# Schematic.net
KiCad netlist of a schematic drawn in Altium Designer
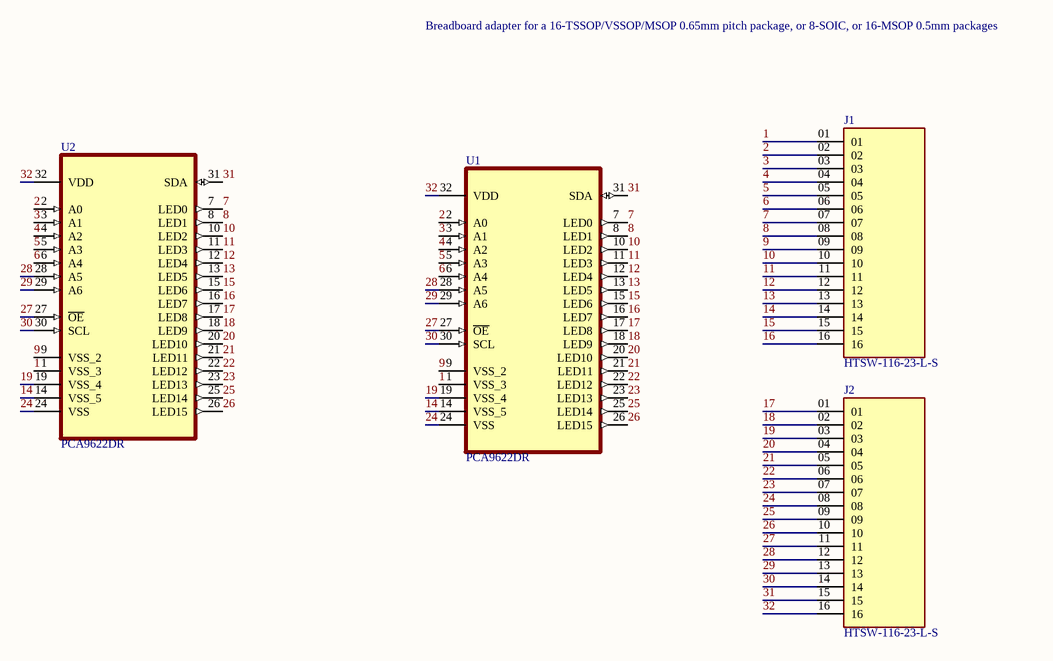
[diagram p0: Schematic.SchDoc]

(export (version "E")
  (design (tool "Eeschema 10.0.6"))
  (components
    (comp (ref "J1")
      (value "HTSW-116-23-L-S")
      (footprint "SAMTEC_HTSW-116-23-L-S")
      (libsource (lib "HTSW-116-23-L-S") (part "HTSW-116-23-L-S"))
    )
    (comp (ref "J2")
      (value "HTSW-116-23-L-S")
      (footprint "SAMTEC_HTSW-116-23-L-S")
      (libsource (lib "HTSW-116-23-L-S") (part "HTSW-116-23-L-S"))
    )
    (comp (ref "U1")
      (value "PCA9622DR")
      (footprint "SOP65P810X110-32N:SOP65P810X110-32N")
      (description "16-bit Fm+ I2C-bus 100 mA 40 V LED driver")
      (libsource (lib "PCA9622DR") (part "PCA9622DR"))
    )
    (comp (ref "U2")
      (value "PCA9622DR")
      (footprint "SOP65P810X110-32N:SOP65P810X110-32N-0.5mm")
      (description "16-bit Fm+ I2C-bus 100 mA 40 V LED driver")
      (libsource (lib "PCA9622DR") (part "PCA9622DR"))
    )
  )
  (nets
    (net (code "1") (name "/1") (class "Default")
      (node (ref "J1") (pin "01") (pinfunction "01_01") (pintype "passive"))
      (node (ref "U1") (pin "1") (pinfunction "VSS_3_1") (pintype "passive"))
      (node (ref "U2") (pin "1") (pinfunction "VSS_3_1") (pintype "passive"))
    )
    (net (code "2") (name "/2") (class "Default")
      (node (ref "J1") (pin "02") (pinfunction "02_02") (pintype "passive"))
      (node (ref "U1") (pin "2") (pinfunction "A0_2") (pintype "input"))
      (node (ref "U2") (pin "2") (pinfunction "A0_2") (pintype "input"))
    )
    (net (code "3") (name "/3") (class "Default")
      (node (ref "J1") (pin "03") (pinfunction "03_03") (pintype "passive"))
      (node (ref "U1") (pin "3") (pinfunction "A1_3") (pintype "input"))
      (node (ref "U2") (pin "3") (pinfunction "A1_3") (pintype "input"))
    )
    (net (code "4") (name "/4") (class "Default")
      (node (ref "J1") (pin "04") (pinfunction "04_04") (pintype "passive"))
      (node (ref "U1") (pin "4") (pinfunction "A2_4") (pintype "input"))
      (node (ref "U2") (pin "4") (pinfunction "A2_4") (pintype "input"))
    )
    (net (code "5") (name "/5") (class "Default")
      (node (ref "J1") (pin "05") (pinfunction "05_05") (pintype "passive"))
      (node (ref "U1") (pin "5") (pinfunction "A3_5") (pintype "input"))
      (node (ref "U2") (pin "5") (pinfunction "A3_5") (pintype "input"))
    )
    (net (code "6") (name "/6") (class "Default")
      (node (ref "J1") (pin "06") (pinfunction "06_06") (pintype "passive"))
      (node (ref "U1") (pin "6") (pinfunction "A4_6") (pintype "input"))
      (node (ref "U2") (pin "6") (pinfunction "A4_6") (pintype "input"))
    )
    (net (code "7") (name "/7") (class "Default")
      (node (ref "J1") (pin "07") (pinfunction "07_07") (pintype "passive"))
      (node (ref "U1") (pin "7") (pinfunction "LED0_7") (pintype "output"))
      (node (ref "U2") (pin "7") (pinfunction "LED0_7") (pintype "output"))
    )
    (net (code "8") (name "/8") (class "Default")
      (node (ref "J1") (pin "08") (pinfunction "08_08") (pintype "passive"))
      (node (ref "U1") (pin "8") (pinfunction "LED1_8") (pintype "output"))
      (node (ref "U2") (pin "8") (pinfunction "LED1_8") (pintype "output"))
    )
    (net (code "9") (name "/9") (class "Default")
      (node (ref "J1") (pin "09") (pinfunction "09_09") (pintype "passive"))
      (node (ref "U1") (pin "9") (pinfunction "VSS_2_9") (pintype "passive"))
      (node (ref "U2") (pin "9") (pinfunction "VSS_2_9") (pintype "passive"))
    )
    (net (code "10") (name "/10") (class "Default")
      (node (ref "J1") (pin "10") (pinfunction "10_10") (pintype "passive"))
      (node (ref "U1") (pin "10") (pinfunction "LED2_10") (pintype "output"))
      (node (ref "U2") (pin "10") (pinfunction "LED2_10") (pintype "output"))
    )
    (net (code "11") (name "/11") (class "Default")
      (node (ref "J1") (pin "11") (pinfunction "11_11") (pintype "passive"))
      (node (ref "U1") (pin "11") (pinfunction "LED3_11") (pintype "output"))
      (node (ref "U2") (pin "11") (pinfunction "LED3_11") (pintype "output"))
    )
    (net (code "12") (name "/12") (class "Default")
      (node (ref "J1") (pin "12") (pinfunction "12_12") (pintype "passive"))
      (node (ref "U1") (pin "12") (pinfunction "LED4_12") (pintype "output"))
      (node (ref "U2") (pin "12") (pinfunction "LED4_12") (pintype "output"))
    )
    (net (code "13") (name "/13") (class "Default")
      (node (ref "J1") (pin "13") (pinfunction "13_13") (pintype "passive"))
      (node (ref "U1") (pin "13") (pinfunction "LED5_13") (pintype "output"))
      (node (ref "U2") (pin "13") (pinfunction "LED5_13") (pintype "output"))
    )
    (net (code "14") (name "/14") (class "Default")
      (node (ref "J1") (pin "14") (pinfunction "14_14") (pintype "passive"))
      (node (ref "U1") (pin "14") (pinfunction "VSS_5_14") (pintype "passive"))
      (node (ref "U2") (pin "14") (pinfunction "VSS_5_14") (pintype "passive"))
    )
    (net (code "15") (name "/15") (class "Default")
      (node (ref "J1") (pin "15") (pinfunction "15_15") (pintype "passive"))
      (node (ref "U1") (pin "15") (pinfunction "LED6_15") (pintype "output"))
      (node (ref "U2") (pin "15") (pinfunction "LED6_15") (pintype "output"))
    )
    (net (code "16") (name "/16") (class "Default")
      (node (ref "J1") (pin "16") (pinfunction "16_16") (pintype "passive"))
      (node (ref "U1") (pin "16") (pinfunction "LED7_16") (pintype "output"))
      (node (ref "U2") (pin "16") (pinfunction "LED7_16") (pintype "output"))
    )
    (net (code "17") (name "/17") (class "Default")
      (node (ref "J2") (pin "01") (pinfunction "01_01") (pintype "passive"))
      (node (ref "U1") (pin "17") (pinfunction "LED8_17") (pintype "output"))
      (node (ref "U2") (pin "17") (pinfunction "LED8_17") (pintype "output"))
    )
    (net (code "18") (name "/18") (class "Default")
      (node (ref "J2") (pin "02") (pinfunction "02_02") (pintype "passive"))
      (node (ref "U1") (pin "18") (pinfunction "LED9_18") (pintype "output"))
      (node (ref "U2") (pin "18") (pinfunction "LED9_18") (pintype "output"))
    )
    (net (code "19") (name "/19") (class "Default")
      (node (ref "J2") (pin "03") (pinfunction "03_03") (pintype "passive"))
      (node (ref "U1") (pin "19") (pinfunction "VSS_4_19") (pintype "passive"))
      (node (ref "U2") (pin "19") (pinfunction "VSS_4_19") (pintype "passive"))
    )
    (net (code "20") (name "/20") (class "Default")
      (node (ref "J2") (pin "04") (pinfunction "04_04") (pintype "passive"))
      (node (ref "U1") (pin "20") (pinfunction "LED10_20") (pintype "output"))
      (node (ref "U2") (pin "20") (pinfunction "LED10_20") (pintype "output"))
    )
    (net (code "21") (name "/21") (class "Default")
      (node (ref "J2") (pin "05") (pinfunction "05_05") (pintype "passive"))
      (node (ref "U1") (pin "21") (pinfunction "LED11_21") (pintype "output"))
      (node (ref "U2") (pin "21") (pinfunction "LED11_21") (pintype "output"))
    )
    (net (code "22") (name "/22") (class "Default")
      (node (ref "J2") (pin "06") (pinfunction "06_06") (pintype "passive"))
      (node (ref "U1") (pin "22") (pinfunction "LED12_22") (pintype "output"))
      (node (ref "U2") (pin "22") (pinfunction "LED12_22") (pintype "output"))
    )
    (net (code "23") (name "/23") (class "Default")
      (node (ref "J2") (pin "07") (pinfunction "07_07") (pintype "passive"))
      (node (ref "U1") (pin "23") (pinfunction "LED13_23") (pintype "output"))
      (node (ref "U2") (pin "23") (pinfunction "LED13_23") (pintype "output"))
    )
    (net (code "24") (name "/24") (class "Default")
      (node (ref "J2") (pin "08") (pinfunction "08_08") (pintype "passive"))
      (node (ref "U1") (pin "24") (pinfunction "VSS_24") (pintype "passive"))
      (node (ref "U2") (pin "24") (pinfunction "VSS_24") (pintype "passive"))
    )
    (net (code "25") (name "/25") (class "Default")
      (node (ref "J2") (pin "09") (pinfunction "09_09") (pintype "passive"))
      (node (ref "U1") (pin "25") (pinfunction "LED14_25") (pintype "output"))
      (node (ref "U2") (pin "25") (pinfunction "LED14_25") (pintype "output"))
    )
    (net (code "26") (name "/26") (class "Default")
      (node (ref "J2") (pin "10") (pinfunction "10_10") (pintype "passive"))
      (node (ref "U1") (pin "26") (pinfunction "LED15_26") (pintype "output"))
      (node (ref "U2") (pin "26") (pinfunction "LED15_26") (pintype "output"))
    )
    (net (code "27") (name "/27") (class "Default")
      (node (ref "J2") (pin "11") (pinfunction "11_11") (pintype "passive"))
      (node (ref "U1") (pin "27") (pinfunction "~{OE}_27") (pintype "input"))
      (node (ref "U2") (pin "27") (pinfunction "~{OE}_27") (pintype "input"))
    )
    (net (code "28") (name "/28") (class "Default")
      (node (ref "J2") (pin "12") (pinfunction "12_12") (pintype "passive"))
      (node (ref "U1") (pin "28") (pinfunction "A5_28") (pintype "input"))
      (node (ref "U2") (pin "28") (pinfunction "A5_28") (pintype "input"))
    )
    (net (code "29") (name "/29") (class "Default")
      (node (ref "J2") (pin "13") (pinfunction "13_13") (pintype "passive"))
      (node (ref "U1") (pin "29") (pinfunction "A6_29") (pintype "input"))
      (node (ref "U2") (pin "29") (pinfunction "A6_29") (pintype "input"))
    )
    (net (code "30") (name "/30") (class "Default")
      (node (ref "J2") (pin "14") (pinfunction "14_14") (pintype "passive"))
      (node (ref "U1") (pin "30") (pinfunction "SCL_30") (pintype "input"))
      (node (ref "U2") (pin "30") (pinfunction "SCL_30") (pintype "input"))
    )
    (net (code "31") (name "/31") (class "Default")
      (node (ref "J2") (pin "15") (pinfunction "15_15") (pintype "passive"))
      (node (ref "U1") (pin "31") (pinfunction "SDA_31") (pintype "bidirectional"))
      (node (ref "U2") (pin "31") (pinfunction "SDA_31") (pintype "bidirectional"))
    )
    (net (code "32") (name "/32") (class "Default")
      (node (ref "J2") (pin "16") (pinfunction "16_16") (pintype "passive"))
      (node (ref "U1") (pin "32") (pinfunction "VDD_32") (pintype "power_in"))
      (node (ref "U2") (pin "32") (pinfunction "VDD_32") (pintype "power_in"))
    )
  )
)
